# tracking_system.net
KiCad netlist of a schematic drawn in EAGLE
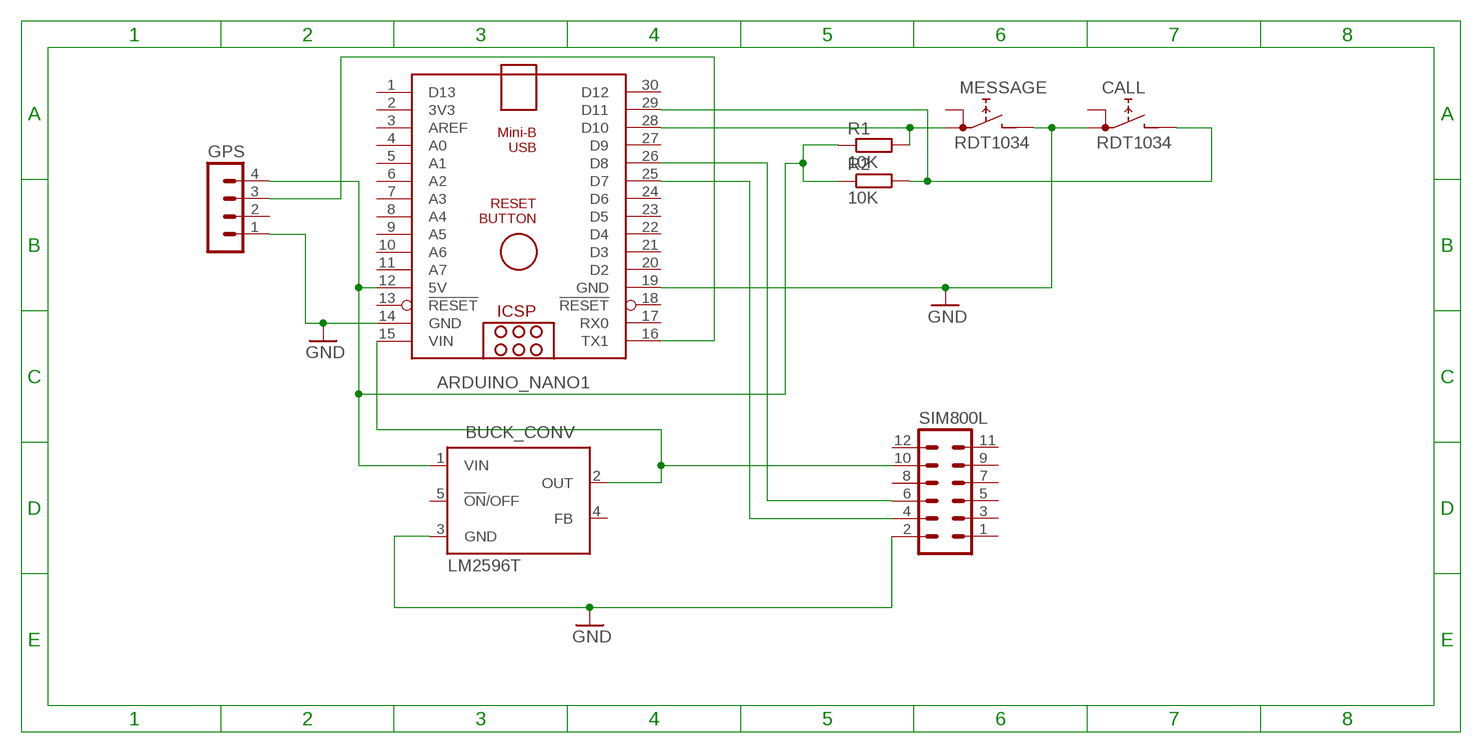
[diagram p0: schematic, sheet 1]

(export (version "E")
  (design (tool "Eeschema 10.0.6"))
  (components
    (comp (ref "ARDUINO_NANO1")
      (value "ARDUINO_NANO")
      (footprint "eagle-import:ARDUINO_NANO")
      (libsource (lib "eagle-import") (part "ARDUINO_NANO"))
    )
    (comp (ref "BUCK_CONV")
      (value "LM2596T")
      (footprint "eagle-import:T05D")
      (fields (field (name "MPN") "LM2596T-ADJ/LF02"))
      (libsource (lib "eagle-import") (part "LM2596T"))
    )
    (comp (ref "CALL")
      (value "RDT1034")
      (footprint "eagle-import:RDT1034")
      (libsource (lib "eagle-import") (part "RDT1034"))
    )
    (comp (ref "GPS")
      (value "MA04-1")
      (footprint "eagle-import:MA04-1")
      (libsource (lib "eagle-import") (part "MA04-1"))
    )
    (comp (ref "MESSAGE")
      (value "RDT1034")
      (footprint "eagle-import:RDT1034")
      (libsource (lib "eagle-import") (part "RDT1034"))
    )
    (comp (ref "R1")
      (value "10K")
      (footprint "eagle-import:0207_10")
      (libsource (lib "eagle-import") (part "R-EU_0207/10"))
    )
    (comp (ref "R2")
      (value "10K")
      (footprint "eagle-import:0207_10")
      (libsource (lib "eagle-import") (part "R-EU_0207/10"))
    )
    (comp (ref "SIM800L")
      (value "MA06-2")
      (footprint "eagle-import:MA06-2")
      (libsource (lib "eagle-import") (part "MA06-2"))
    )
  )
  (nets
    (net (code "1") (name "GND") (class "Default")
      (node (ref "ARDUINO_NANO1") (pin "14") (pinfunction "GND_14") (pintype "power_in"))
      (node (ref "ARDUINO_NANO1") (pin "19") (pinfunction "GND_19") (pintype "power_in"))
      (node (ref "BUCK_CONV") (pin "3") (pinfunction "GND_3") (pintype "power_in"))
      (node (ref "CALL") (pin "A1") (pinfunction "A1_A1") (pintype "passive"))
      (node (ref "GPS") (pin "1") (pinfunction "1_1") (pintype "passive"))
      (node (ref "MESSAGE") (pin "B") (pinfunction "B_B") (pintype "passive"))
      (node (ref "SIM800L") (pin "2") (pinfunction "2_2") (pintype "passive"))
    )
    (net (code "2") (name "Net-(ARDUINO_NANO1-5V)") (class "Default")
      (node (ref "ARDUINO_NANO1") (pin "12") (pinfunction "5V_12") (pintype "power_in"))
      (node (ref "BUCK_CONV") (pin "1") (pinfunction "VIN_1") (pintype "input"))
      (node (ref "GPS") (pin "4") (pinfunction "4_4") (pintype "passive"))
      (node (ref "R1") (pin "1") (pinfunction "1_1") (pintype "passive"))
      (node (ref "R2") (pin "1") (pinfunction "1_1") (pintype "passive"))
    )
    (net (code "3") (name "Net-(ARDUINO_NANO1-D7)") (class "Default")
      (node (ref "ARDUINO_NANO1") (pin "25") (pinfunction "D7_25") (pintype "bidirectional"))
      (node (ref "SIM800L") (pin "4") (pinfunction "4_4") (pintype "passive"))
    )
    (net (code "4") (name "Net-(ARDUINO_NANO1-D8)") (class "Default")
      (node (ref "ARDUINO_NANO1") (pin "26") (pinfunction "D8_26") (pintype "bidirectional"))
      (node (ref "SIM800L") (pin "6") (pinfunction "6_6") (pintype "passive"))
    )
    (net (code "5") (name "Net-(ARDUINO_NANO1-D10)") (class "Default")
      (node (ref "ARDUINO_NANO1") (pin "28") (pinfunction "D10_28") (pintype "bidirectional"))
      (node (ref "MESSAGE") (pin "A1") (pinfunction "A1_A1") (pintype "passive"))
      (node (ref "R1") (pin "2") (pinfunction "2_2") (pintype "passive"))
    )
    (net (code "6") (name "Net-(ARDUINO_NANO1-D11)") (class "Default")
      (node (ref "ARDUINO_NANO1") (pin "29") (pinfunction "D11_29") (pintype "bidirectional"))
      (node (ref "CALL") (pin "B") (pinfunction "B_B") (pintype "passive"))
      (node (ref "R2") (pin "2") (pinfunction "2_2") (pintype "passive"))
    )
    (net (code "7") (name "Net-(ARDUINO_NANO1-TX1)") (class "Default")
      (node (ref "ARDUINO_NANO1") (pin "16") (pinfunction "TX1_16") (pintype "bidirectional"))
      (node (ref "GPS") (pin "3") (pinfunction "3_3") (pintype "passive"))
    )
    (net (code "8") (name "Net-(ARDUINO_NANO1-VIN)") (class "Default")
      (node (ref "ARDUINO_NANO1") (pin "15") (pinfunction "VIN_15") (pintype "power_in"))
      (node (ref "BUCK_CONV") (pin "2") (pinfunction "OUT_2") (pintype "output"))
      (node (ref "SIM800L") (pin "10") (pinfunction "10_10") (pintype "passive"))
    )
    (net (code "9") (name "unconnected-(ARDUINO_NANO1-3V3-Pad2)") (class "Default")
      (node (ref "ARDUINO_NANO1") (pin "2") (pinfunction "3V3_2") (pintype "output"))
    )
    (net (code "10") (name "unconnected-(ARDUINO_NANO1-A0-Pad4)") (class "Default")
      (node (ref "ARDUINO_NANO1") (pin "4") (pinfunction "A0_4") (pintype "bidirectional"))
    )
    (net (code "11") (name "unconnected-(ARDUINO_NANO1-A1-Pad5)") (class "Default")
      (node (ref "ARDUINO_NANO1") (pin "5") (pinfunction "A1_5") (pintype "bidirectional"))
    )
    (net (code "12") (name "unconnected-(ARDUINO_NANO1-A2-Pad6)") (class "Default")
      (node (ref "ARDUINO_NANO1") (pin "6") (pinfunction "A2_6") (pintype "bidirectional"))
    )
    (net (code "13") (name "unconnected-(ARDUINO_NANO1-A3-Pad7)") (class "Default")
      (node (ref "ARDUINO_NANO1") (pin "7") (pinfunction "A3_7") (pintype "bidirectional"))
    )
    (net (code "14") (name "unconnected-(ARDUINO_NANO1-A4-Pad8)") (class "Default")
      (node (ref "ARDUINO_NANO1") (pin "8") (pinfunction "A4_8") (pintype "bidirectional"))
    )
    (net (code "15") (name "unconnected-(ARDUINO_NANO1-A5-Pad9)") (class "Default")
      (node (ref "ARDUINO_NANO1") (pin "9") (pinfunction "A5_9") (pintype "bidirectional"))
    )
    (net (code "16") (name "unconnected-(ARDUINO_NANO1-A6-Pad10)") (class "Default")
      (node (ref "ARDUINO_NANO1") (pin "10") (pinfunction "A6_10") (pintype "bidirectional"))
    )
    (net (code "17") (name "unconnected-(ARDUINO_NANO1-A7-Pad11)") (class "Default")
      (node (ref "ARDUINO_NANO1") (pin "11") (pinfunction "A7_11") (pintype "bidirectional"))
    )
    (net (code "18") (name "unconnected-(ARDUINO_NANO1-AREF-Pad3)") (class "Default")
      (node (ref "ARDUINO_NANO1") (pin "3") (pinfunction "AREF_3") (pintype "input"))
    )
    (net (code "19") (name "unconnected-(ARDUINO_NANO1-D2-Pad20)") (class "Default")
      (node (ref "ARDUINO_NANO1") (pin "20") (pinfunction "D2_20") (pintype "bidirectional"))
    )
    (net (code "20") (name "unconnected-(ARDUINO_NANO1-D3-Pad21)") (class "Default")
      (node (ref "ARDUINO_NANO1") (pin "21") (pinfunction "D3_21") (pintype "bidirectional"))
    )
    (net (code "21") (name "unconnected-(ARDUINO_NANO1-D4-Pad22)") (class "Default")
      (node (ref "ARDUINO_NANO1") (pin "22") (pinfunction "D4_22") (pintype "bidirectional"))
    )
    (net (code "22") (name "unconnected-(ARDUINO_NANO1-D5-Pad23)") (class "Default")
      (node (ref "ARDUINO_NANO1") (pin "23") (pinfunction "D5_23") (pintype "bidirectional"))
    )
    (net (code "23") (name "unconnected-(ARDUINO_NANO1-D6-Pad24)") (class "Default")
      (node (ref "ARDUINO_NANO1") (pin "24") (pinfunction "D6_24") (pintype "bidirectional"))
    )
    (net (code "24") (name "unconnected-(ARDUINO_NANO1-D9-Pad27)") (class "Default")
      (node (ref "ARDUINO_NANO1") (pin "27") (pinfunction "D9_27") (pintype "bidirectional"))
    )
    (net (code "25") (name "unconnected-(ARDUINO_NANO1-D12-Pad30)") (class "Default")
      (node (ref "ARDUINO_NANO1") (pin "30") (pinfunction "D12_30") (pintype "bidirectional"))
    )
    (net (code "26") (name "unconnected-(ARDUINO_NANO1-D13-Pad1)") (class "Default")
      (node (ref "ARDUINO_NANO1") (pin "1") (pinfunction "D13_1") (pintype "bidirectional"))
    )
    (net (code "27") (name "unconnected-(ARDUINO_NANO1-RX0-Pad17)") (class "Default")
      (node (ref "ARDUINO_NANO1") (pin "17") (pinfunction "RX0_17") (pintype "bidirectional"))
    )
    (net (code "28") (name "unconnected-(ARDUINO_NANO1-~{RESET}-Pad13)") (class "Default")
      (node (ref "ARDUINO_NANO1") (pin "13") (pinfunction "~{RESET}_13") (pintype "input"))
    )
    (net (code "29") (name "unconnected-(ARDUINO_NANO1-~{RESET}-Pad18)") (class "Default")
      (node (ref "ARDUINO_NANO1") (pin "18") (pinfunction "~{RESET}_18") (pintype "input"))
    )
    (net (code "30") (name "unconnected-(BUCK_CONV-FB-Pad4)") (class "Default")
      (node (ref "BUCK_CONV") (pin "4") (pinfunction "FB_4") (pintype "input"))
    )
    (net (code "31") (name "unconnected-(BUCK_CONV-~{ON}{slash}OFF-Pad5)") (class "Default")
      (node (ref "BUCK_CONV") (pin "5") (pinfunction "~{ON}/OFF_5") (pintype "input"))
    )
    (net (code "32") (name "unconnected-(CALL-PadA)") (class "Default")
      (node (ref "CALL") (pin "A") (pinfunction "A_A") (pintype "passive"))
    )
    (net (code "33") (name "unconnected-(GPS-Pad2)") (class "Default")
      (node (ref "GPS") (pin "2") (pinfunction "2_2") (pintype "passive"))
    )
    (net (code "34") (name "unconnected-(MESSAGE-PadA)") (class "Default")
      (node (ref "MESSAGE") (pin "A") (pinfunction "A_A") (pintype "passive"))
    )
    (net (code "35") (name "unconnected-(SIM800L-Pad1)") (class "Default")
      (node (ref "SIM800L") (pin "1") (pinfunction "1_1") (pintype "passive"))
    )
    (net (code "36") (name "unconnected-(SIM800L-Pad3)") (class "Default")
      (node (ref "SIM800L") (pin "3") (pinfunction "3_3") (pintype "passive"))
    )
    (net (code "37") (name "unconnected-(SIM800L-Pad5)") (class "Default")
      (node (ref "SIM800L") (pin "5") (pinfunction "5_5") (pintype "passive"))
    )
    (net (code "38") (name "unconnected-(SIM800L-Pad7)") (class "Default")
      (node (ref "SIM800L") (pin "7") (pinfunction "7_7") (pintype "passive"))
    )
    (net (code "39") (name "unconnected-(SIM800L-Pad8)") (class "Default")
      (node (ref "SIM800L") (pin "8") (pinfunction "8_8") (pintype "passive"))
    )
    (net (code "40") (name "unconnected-(SIM800L-Pad9)") (class "Default")
      (node (ref "SIM800L") (pin "9") (pinfunction "9_9") (pintype "passive"))
    )
    (net (code "41") (name "unconnected-(SIM800L-Pad11)") (class "Default")
      (node (ref "SIM800L") (pin "11") (pinfunction "11_11") (pintype "passive"))
    )
    (net (code "42") (name "unconnected-(SIM800L-Pad12)") (class "Default")
      (node (ref "SIM800L") (pin "12") (pinfunction "12_12") (pintype "passive"))
    )
  )
)
